# v1_E7.net
KiCad netlist of a schematic drawn in EAGLE
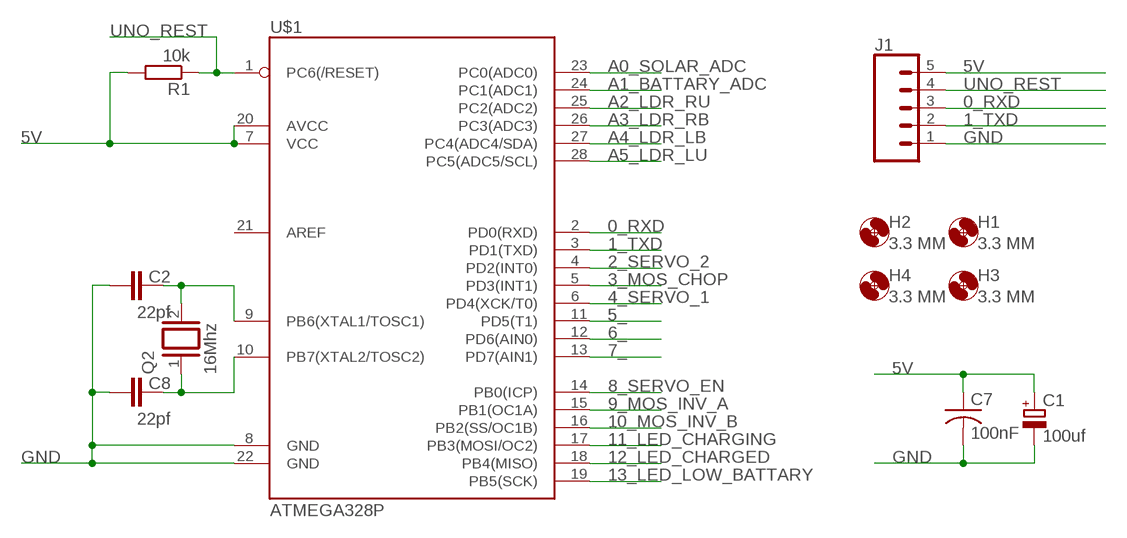
[diagram p0: schematic, sheet 1]
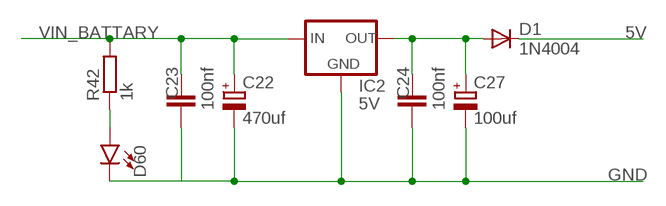
[diagram p1: schematic, sheet 2]
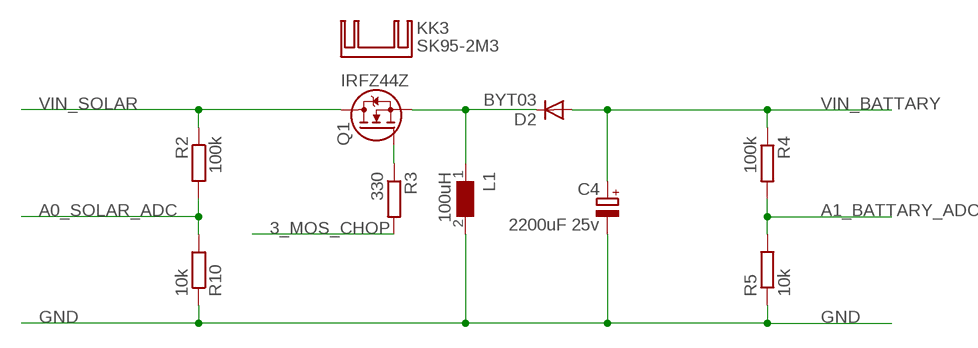
[diagram p2: schematic, sheet 3]
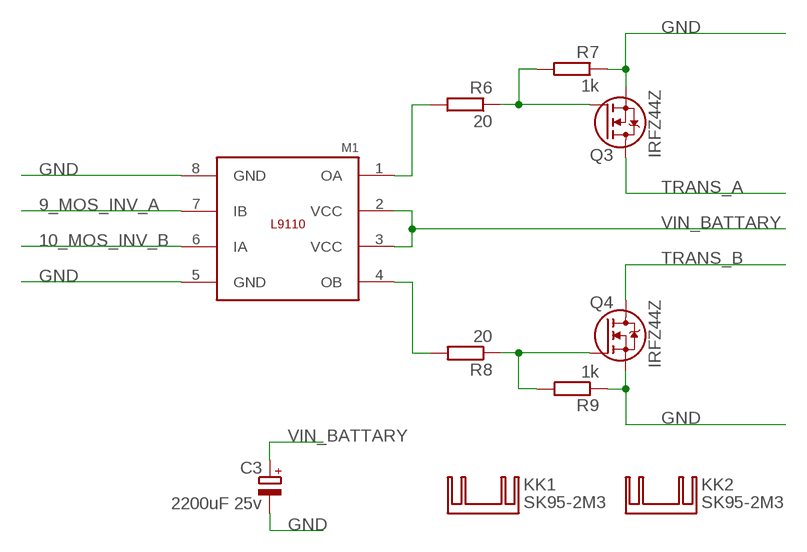
[diagram p3: schematic, sheet 4]
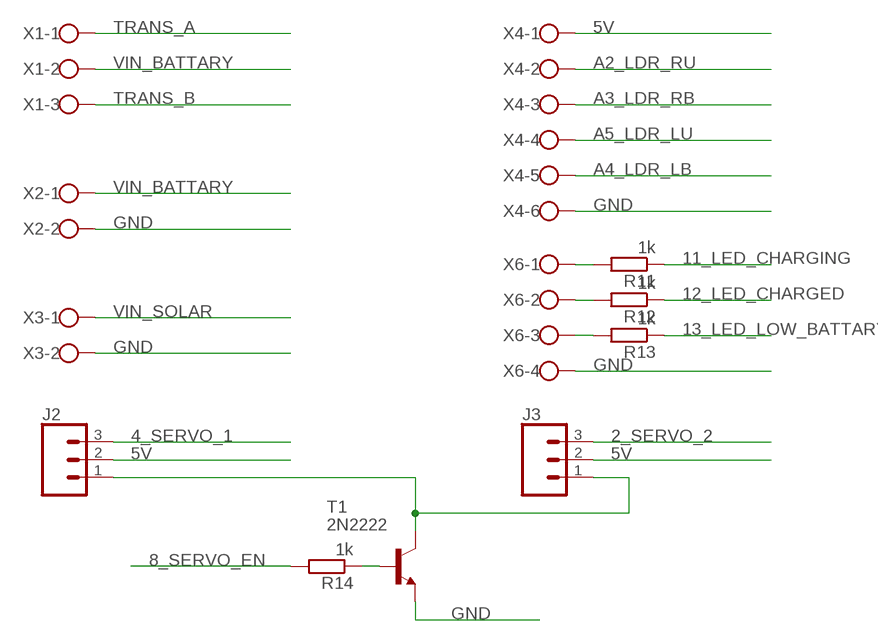
[diagram p4: schematic, sheet 5]

(export (version "E")
  (design (tool "Eeschema 10.0.6"))
  (components
    (comp (ref "C4")
      (value "2200uF 25v")
      (footprint "eagle-import:E5-13")
      (libsource (lib "eagle-import") (part "rcl@1_CPOL-EUE5-13"))
    )
    (comp (ref "D2")
      (value "BYT03")
      (footprint "eagle-import:DO27-15")
      (libsource (lib "eagle-import") (part "BYT03"))
    )
    (comp (ref "KK3")
      (value "SK95-2M3")
      (footprint "eagle-import:SK95-2M3")
      (libsource (lib "eagle-import") (part "SK95-2M3"))
    )
    (comp (ref "L1")
      (value "100uH")
      (footprint "eagle-import:WE-ZB")
      (libsource (lib "eagle-import") (part "WE-ZB"))
    )
    (comp (ref "Q1")
      (value "IRFZ44Z")
      (footprint "eagle-import:TO220V")
      (libsource (lib "eagle-import") (part "IRFZ44Z"))
    )
    (comp (ref "R2")
      (value "100k")
      (footprint "eagle-import:0207_10")
      (libsource (lib "eagle-import") (part "R-EU_0207/10"))
    )
    (comp (ref "R3")
      (value "330")
      (footprint "eagle-import:0207_10")
      (libsource (lib "eagle-import") (part "R-EU_0207/10"))
    )
    (comp (ref "R4")
      (value "100k")
      (footprint "eagle-import:0207_10")
      (libsource (lib "eagle-import") (part "R-EU_0207/10"))
    )
    (comp (ref "R5")
      (value "10k")
      (footprint "eagle-import:0207_10")
      (libsource (lib "eagle-import") (part "R-EU_0207/10"))
    )
    (comp (ref "R10")
      (value "10k")
      (footprint "eagle-import:0207_10")
      (libsource (lib "eagle-import") (part "R-EU_0207/10"))
    )
    (comp (ref "C1")
      (value "100uf")
      (footprint "eagle-import:E3,5-8")
      (libsource (lib "eagle-import") (part "CPOL-EUE3.5-8"))
    )
    (comp (ref "C2")
      (value "22pf")
      (footprint "eagle-import:C050-030X075")
      (libsource (lib "eagle-import") (part "C-EU050-030X075"))
    )
    (comp (ref "C7")
      (value "100nF")
      (footprint "eagle-import:C050-035X075")
      (libsource (lib "eagle-import") (part "C-US050-035X075"))
    )
    (comp (ref "C8")
      (value "22pf")
      (footprint "eagle-import:C050-030X075")
      (libsource (lib "eagle-import") (part "C-EU050-030X075"))
    )
    (comp (ref "H1")
      (value "3.3 MM")
      (footprint "eagle-import:3,3")
      (libsource (lib "eagle-import") (part "MOUNT-HOLE3.3"))
    )
    (comp (ref "H2")
      (value "3.3 MM")
      (footprint "eagle-import:3,3")
      (libsource (lib "eagle-import") (part "MOUNT-HOLE3.3"))
    )
    (comp (ref "H3")
      (value "3.3 MM")
      (footprint "eagle-import:3,3")
      (libsource (lib "eagle-import") (part "MOUNT-HOLE3.3"))
    )
    (comp (ref "H4")
      (value "3.3 MM")
      (footprint "eagle-import:3,3")
      (libsource (lib "eagle-import") (part "MOUNT-HOLE3.3"))
    )
    (comp (ref "J1")
      (value "CONN_05JST-VERT")
      (footprint "eagle-import:JST-5-PTH-VERT")
      (libsource (lib "eagle-import") (part "CONN_05JST-VERT"))
    )
    (comp (ref "Q2")
      (value "16Mhz")
      (footprint "eagle-import:QS")
      (libsource (lib "eagle-import") (part "XTAL/S"))
    )
    (comp (ref "R1")
      (value "10k")
      (footprint "eagle-import:0207_10")
      (libsource (lib "eagle-import") (part "R-EU_0207/10"))
    )
    (comp (ref "U$1")
      (value "ATMEGA328P")
      (footprint "eagle-import:DIL-28-3")
      (libsource (lib "eagle-import") (part "ATMEGA328P_PDIP"))
    )
    (comp (ref "C22")
      (value "470uf")
      (footprint "eagle-import:E3,5-8")
      (libsource (lib "eagle-import") (part "CPOL-EUE3.5-8"))
    )
    (comp (ref "C23")
      (value "100nf")
      (footprint "eagle-import:C050-030X075")
      (libsource (lib "eagle-import") (part "C-EU050-030X075"))
    )
    (comp (ref "C24")
      (value "100nf")
      (footprint "eagle-import:C050-030X075")
      (libsource (lib "eagle-import") (part "C-EU050-030X075"))
    )
    (comp (ref "C27")
      (value "100uf")
      (footprint "eagle-import:E3,5-8")
      (libsource (lib "eagle-import") (part "CPOL-EUE3.5-8"))
    )
    (comp (ref "D1")
      (value "1N4004")
      (footprint "eagle-import:DO41-10")
      (libsource (lib "eagle-import") (part "1N4004"))
    )
    (comp (ref "D60")
      (value "LED5MM")
      (footprint "eagle-import:LED_5MM")
      (libsource (lib "eagle-import") (part "LED5MM"))
    )
    (comp (ref "IC2")
      (value "5V")
      (footprint "eagle-import:78XXL")
      (libsource (lib "eagle-import") (part "V_REG_78XXSIDE"))
    )
    (comp (ref "R42")
      (value "1k")
      (footprint "eagle-import:0207_10")
      (libsource (lib "eagle-import") (part "R-EU_0207/10"))
    )
    (comp (ref "C3")
      (value "2200uF 25v")
      (footprint "eagle-import:E5-13")
      (libsource (lib "eagle-import") (part "rcl@1_CPOL-EUE5-13"))
    )
    (comp (ref "KK1")
      (value "SK95-2M3")
      (footprint "eagle-import:SK95-2M3")
      (libsource (lib "eagle-import") (part "SK95-2M3"))
    )
    (comp (ref "KK2")
      (value "SK95-2M3")
      (footprint "eagle-import:SK95-2M3")
      (libsource (lib "eagle-import") (part "SK95-2M3"))
    )
    (comp (ref "M1")
      (value "L9110")
      (footprint "eagle-import:SO8P")
      (libsource (lib "eagle-import") (part "L9110"))
    )
    (comp (ref "Q3")
      (value "IRFZ44Z")
      (footprint "eagle-import:TO220V")
      (libsource (lib "eagle-import") (part "IRFZ44Z"))
    )
    (comp (ref "Q4")
      (value "IRFZ44Z")
      (footprint "eagle-import:TO220V")
      (libsource (lib "eagle-import") (part "IRFZ44Z"))
    )
    (comp (ref "R6")
      (value "20")
      (footprint "eagle-import:0207_10")
      (libsource (lib "eagle-import") (part "R-EU_0207/10"))
    )
    (comp (ref "R7")
      (value "1k")
      (footprint "eagle-import:0207_10")
      (libsource (lib "eagle-import") (part "R-EU_0207/10"))
    )
    (comp (ref "R8")
      (value "20")
      (footprint "eagle-import:0207_10")
      (libsource (lib "eagle-import") (part "R-EU_0207/10"))
    )
    (comp (ref "R9")
      (value "1k")
      (footprint "eagle-import:0207_10")
      (libsource (lib "eagle-import") (part "R-EU_0207/10"))
    )
    (comp (ref "J2")
      (value "CONN_03JST-PTH-VERT")
      (footprint "eagle-import:JST-3-PTH-VERT")
      (libsource (lib "eagle-import") (part "CONN_03JST-PTH-VERT"))
    )
    (comp (ref "J3")
      (value "CONN_03JST-PTH-VERT")
      (footprint "eagle-import:JST-3-PTH-VERT")
      (libsource (lib "eagle-import") (part "CONN_03JST-PTH-VERT"))
    )
    (comp (ref "R11")
      (value "1k")
      (footprint "eagle-import:0207_10")
      (libsource (lib "eagle-import") (part "R-EU_0207/10"))
    )
    (comp (ref "R12")
      (value "1k")
      (footprint "eagle-import:0207_10")
      (libsource (lib "eagle-import") (part "R-EU_0207/10"))
    )
    (comp (ref "R13")
      (value "1k")
      (footprint "eagle-import:0207_10")
      (libsource (lib "eagle-import") (part "R-EU_0207/10"))
    )
    (comp (ref "R14")
      (value "1k")
      (footprint "eagle-import:0207_10")
      (libsource (lib "eagle-import") (part "R-EU_0207/10"))
    )
    (comp (ref "T1")
      (value "2N2222")
      (footprint "eagle-import:TO92-EBC-OVAL")
      (libsource (lib "eagle-import") (part "2N2222"))
    )
    (comp (ref "X1")
      (value "W237-103")
      (footprint "eagle-import:W237-103")
      (fields (field (name "MPN") "237-103"))
      (libsource (lib "eagle-import") (part "W237-103"))
    )
    (comp (ref "X2")
      (value "W237-102")
      (footprint "eagle-import:W237-102")
      (fields (field (name "MPN") "237-102"))
      (libsource (lib "eagle-import") (part "W237-102"))
    )
    (comp (ref "X3")
      (value "W237-102")
      (footprint "eagle-import:W237-102")
      (fields (field (name "MPN") "237-102"))
      (libsource (lib "eagle-import") (part "W237-102"))
    )
    (comp (ref "X4")
      (value "W237-6")
      (footprint "eagle-import:W237-6")
      (libsource (lib "eagle-import") (part "W237-6"))
    )
    (comp (ref "X6")
      (value "W237-4")
      (footprint "eagle-import:W237-4")
      (libsource (lib "eagle-import") (part "W237-4"))
    )
  )
  (nets
    (net (code "1") (name "0_RXD") (class "Default")
      (node (ref "J1") (pin "3") (pinfunction "3_3") (pintype "passive"))
      (node (ref "U$1") (pin "2") (pinfunction "PD0(RXD)_2") (pintype "bidirectional"))
    )
    (net (code "2") (name "1_TXD") (class "Default")
      (node (ref "J1") (pin "2") (pinfunction "2_2") (pintype "passive"))
      (node (ref "U$1") (pin "3") (pinfunction "PD1(TXD)_3") (pintype "bidirectional"))
    )
    (net (code "3") (name "2_SERVO_2") (class "Default")
      (node (ref "J3") (pin "3") (pinfunction "3_3") (pintype "passive"))
      (node (ref "U$1") (pin "4") (pinfunction "PD2(INT0)_4") (pintype "bidirectional"))
    )
    (net (code "4") (name "3_MOS_CHOP") (class "Default")
      (node (ref "R3") (pin "2") (pinfunction "2_2") (pintype "passive"))
      (node (ref "U$1") (pin "5") (pinfunction "PD3(INT1)_5") (pintype "bidirectional"))
    )
    (net (code "5") (name "4_SERVO_1") (class "Default")
      (node (ref "J2") (pin "3") (pinfunction "3_3") (pintype "passive"))
      (node (ref "U$1") (pin "6") (pinfunction "PD4(XCK/T0)_6") (pintype "bidirectional"))
    )
    (net (code "6") (name "5V") (class "Default")
      (node (ref "C1") (pin "+") (pinfunction "+_+") (pintype "passive"))
      (node (ref "C7") (pin "1") (pinfunction "1_1") (pintype "passive"))
      (node (ref "D1") (pin "C") (pinfunction "C_C") (pintype "passive"))
      (node (ref "J1") (pin "5") (pinfunction "5_5") (pintype "passive"))
      (node (ref "J2") (pin "2") (pinfunction "2_2") (pintype "passive"))
      (node (ref "J3") (pin "2") (pinfunction "2_2") (pintype "passive"))
      (node (ref "R1") (pin "2") (pinfunction "2_2") (pintype "passive"))
      (node (ref "U$1") (pin "20") (pinfunction "AVCC_20") (pintype "bidirectional"))
      (node (ref "U$1") (pin "7") (pinfunction "VCC_7") (pintype "bidirectional"))
      (node (ref "X4") (pin "1") (pinfunction "KL_1") (pintype "passive"))
    )
    (net (code "7") (name "5_") (class "Default")
      (node (ref "U$1") (pin "11") (pinfunction "PD5(T1)_11") (pintype "bidirectional"))
    )
    (net (code "8") (name "6_") (class "Default")
      (node (ref "U$1") (pin "12") (pinfunction "PD6(AIN0)_12") (pintype "bidirectional"))
    )
    (net (code "9") (name "7_") (class "Default")
      (node (ref "U$1") (pin "13") (pinfunction "PD7(AIN1)_13") (pintype "bidirectional"))
    )
    (net (code "10") (name "8_SERVO_EN") (class "Default")
      (node (ref "R14") (pin "2") (pinfunction "2_2") (pintype "passive"))
      (node (ref "U$1") (pin "14") (pinfunction "PB0(ICP)_14") (pintype "bidirectional"))
    )
    (net (code "11") (name "9_MOS_INV_A") (class "Default")
      (node (ref "M1") (pin "7") (pinfunction "IB_7") (pintype "bidirectional"))
      (node (ref "U$1") (pin "15") (pinfunction "PB1(OC1A)_15") (pintype "bidirectional"))
    )
    (net (code "12") (name "10_MOS_INV_B") (class "Default")
      (node (ref "M1") (pin "6") (pinfunction "IA_6") (pintype "bidirectional"))
      (node (ref "U$1") (pin "16") (pinfunction "PB2(SS/OC1B)_16") (pintype "bidirectional"))
    )
    (net (code "13") (name "11_LED_CHARGING") (class "Default")
      (node (ref "R11") (pin "1") (pinfunction "1_1") (pintype "passive"))
      (node (ref "U$1") (pin "17") (pinfunction "PB3(MOSI/OC2)_17") (pintype "bidirectional"))
    )
    (net (code "14") (name "12_LED_CHARGED") (class "Default")
      (node (ref "R12") (pin "1") (pinfunction "1_1") (pintype "passive"))
      (node (ref "U$1") (pin "18") (pinfunction "PB4(MISO)_18") (pintype "bidirectional"))
    )
    (net (code "15") (name "13_LED_LOW_BATTARY") (class "Default")
      (node (ref "R13") (pin "1") (pinfunction "1_1") (pintype "passive"))
      (node (ref "U$1") (pin "19") (pinfunction "PB5(SCK)_19") (pintype "bidirectional"))
    )
    (net (code "16") (name "A0_SOLAR_ADC") (class "Default")
      (node (ref "R10") (pin "2") (pinfunction "2_2") (pintype "passive"))
      (node (ref "R2") (pin "2") (pinfunction "2_2") (pintype "passive"))
      (node (ref "U$1") (pin "23") (pinfunction "PC0(ADC0)_23") (pintype "bidirectional"))
    )
    (net (code "17") (name "A1_BATTARY_ADC") (class "Default")
      (node (ref "R4") (pin "2") (pinfunction "2_2") (pintype "passive"))
      (node (ref "R5") (pin "2") (pinfunction "2_2") (pintype "passive"))
      (node (ref "U$1") (pin "24") (pinfunction "PC1(ADC1)_24") (pintype "bidirectional"))
    )
    (net (code "18") (name "A2_LDR_RU") (class "Default")
      (node (ref "U$1") (pin "25") (pinfunction "PC2(ADC2)_25") (pintype "bidirectional"))
      (node (ref "X4") (pin "2") (pinfunction "KL_2") (pintype "passive"))
    )
    (net (code "19") (name "A3_LDR_RB") (class "Default")
      (node (ref "U$1") (pin "26") (pinfunction "PC3(ADC3)_26") (pintype "bidirectional"))
      (node (ref "X4") (pin "3") (pinfunction "KL_3") (pintype "passive"))
    )
    (net (code "20") (name "A4_LDR_LB") (class "Default")
      (node (ref "U$1") (pin "27") (pinfunction "PC4(ADC4/SDA)_27") (pintype "bidirectional"))
      (node (ref "X4") (pin "5") (pinfunction "KL_5") (pintype "passive"))
    )
    (net (code "21") (name "A5_LDR_LU") (class "Default")
      (node (ref "U$1") (pin "28") (pinfunction "PC5(ADC5/SCL)_28") (pintype "bidirectional"))
      (node (ref "X4") (pin "4") (pinfunction "KL_4") (pintype "passive"))
    )
    (net (code "22") (name "GND") (class "Default")
      (node (ref "C1") (pin "-") (pinfunction "-_-") (pintype "passive"))
      (node (ref "C2") (pin "1") (pinfunction "1_1") (pintype "passive"))
      (node (ref "C22") (pin "-") (pinfunction "-_-") (pintype "passive"))
      (node (ref "C23") (pin "1") (pinfunction "1_1") (pintype "passive"))
      (node (ref "C24") (pin "1") (pinfunction "1_1") (pintype "passive"))
      (node (ref "C27") (pin "-") (pinfunction "-_-") (pintype "passive"))
      (node (ref "C3") (pin "-") (pinfunction "-_-") (pintype "passive"))
      (node (ref "C4") (pin "-") (pinfunction "-_-") (pintype "passive"))
      (node (ref "C7") (pin "2") (pinfunction "2_2") (pintype "passive"))
      (node (ref "C8") (pin "1") (pinfunction "1_1") (pintype "passive"))
      (node (ref "D60") (pin "K") (pinfunction "C_K") (pintype "passive"))
      (node (ref "IC2") (pin "GND") (pinfunction "GND_GND") (pintype "input"))
      (node (ref "J1") (pin "1") (pinfunction "1_1") (pintype "passive"))
      (node (ref "L1") (pin "2") (pinfunction "2_2") (pintype "passive"))
      (node (ref "M1") (pin "5") (pinfunction "GND_5") (pintype "bidirectional"))
      (node (ref "M1") (pin "8") (pinfunction "GND_8") (pintype "bidirectional"))
      (node (ref "Q3") (pin "3") (pinfunction "S_3") (pintype "passive"))
      (node (ref "Q4") (pin "3") (pinfunction "S_3") (pintype "passive"))
      (node (ref "R10") (pin "1") (pinfunction "1_1") (pintype "passive"))
      (node (ref "R5") (pin "1") (pinfunction "1_1") (pintype "passive"))
      (node (ref "R7") (pin "1") (pinfunction "1_1") (pintype "passive"))
      (node (ref "R9") (pin "1") (pinfunction "1_1") (pintype "passive"))
      (node (ref "T1") (pin "E") (pinfunction "E_E") (pintype "passive"))
      (node (ref "U$1") (pin "22") (pinfunction "GND_22") (pintype "bidirectional"))
      (node (ref "U$1") (pin "8") (pinfunction "GND_8") (pintype "bidirectional"))
      (node (ref "X2") (pin "2") (pinfunction "KL_2") (pintype "passive"))
      (node (ref "X3") (pin "2") (pinfunction "KL_2") (pintype "passive"))
      (node (ref "X4") (pin "6") (pinfunction "KL_6") (pintype "passive"))
      (node (ref "X6") (pin "4") (pinfunction "KL_4") (pintype "passive"))
    )
    (net (code "23") (name "Net-(C24-Pad2)") (class "Default")
      (node (ref "C24") (pin "2") (pinfunction "2_2") (pintype "passive"))
      (node (ref "C27") (pin "+") (pinfunction "+_+") (pintype "passive"))
      (node (ref "D1") (pin "A") (pinfunction "A_A") (pintype "passive"))
      (node (ref "IC2") (pin "OUT") (pinfunction "OUT_OUT") (pintype "output"))
    )
    (net (code "24") (name "Net-(D60-PadA)") (class "Default")
      (node (ref "D60") (pin "A") (pinfunction "A_A") (pintype "passive"))
      (node (ref "R42") (pin "1") (pinfunction "1_1") (pintype "passive"))
    )
    (net (code "25") (name "Net-(J2-Pad1)") (class "Default")
      (node (ref "J2") (pin "1") (pinfunction "1_1") (pintype "passive"))
      (node (ref "J3") (pin "1") (pinfunction "1_1") (pintype "passive"))
      (node (ref "T1") (pin "C") (pinfunction "C_C") (pintype "passive"))
    )
    (net (code "26") (name "Net-(M1-OA)") (class "Default")
      (node (ref "M1") (pin "1") (pinfunction "OA_1") (pintype "bidirectional"))
      (node (ref "R6") (pin "2") (pinfunction "2_2") (pintype "passive"))
    )
    (net (code "27") (name "Net-(M1-OB)") (class "Default")
      (node (ref "M1") (pin "4") (pinfunction "OB_4") (pintype "bidirectional"))
      (node (ref "R8") (pin "2") (pinfunction "2_2") (pintype "passive"))
    )
    (net (code "28") (name "Net-(Q1-G)") (class "Default")
      (node (ref "Q1") (pin "1") (pinfunction "G_1") (pintype "passive"))
      (node (ref "R3") (pin "1") (pinfunction "1_1") (pintype "passive"))
    )
    (net (code "29") (name "Net-(Q1-S)") (class "Default")
      (node (ref "D2") (pin "C") (pinfunction "C_C") (pintype "passive"))
      (node (ref "L1") (pin "1") (pinfunction "1_1") (pintype "passive"))
      (node (ref "Q1") (pin "3") (pinfunction "S_3") (pintype "passive"))
    )
    (net (code "30") (name "Net-(Q3-G)") (class "Default")
      (node (ref "Q3") (pin "1") (pinfunction "G_1") (pintype "passive"))
      (node (ref "R6") (pin "1") (pinfunction "1_1") (pintype "passive"))
      (node (ref "R7") (pin "2") (pinfunction "2_2") (pintype "passive"))
    )
    (net (code "31") (name "Net-(Q4-G)") (class "Default")
      (node (ref "Q4") (pin "1") (pinfunction "G_1") (pintype "passive"))
      (node (ref "R8") (pin "1") (pinfunction "1_1") (pintype "passive"))
      (node (ref "R9") (pin "2") (pinfunction "2_2") (pintype "passive"))
    )
    (net (code "32") (name "Net-(R14-Pad1)") (class "Default")
      (node (ref "R14") (pin "1") (pinfunction "1_1") (pintype "passive"))
      (node (ref "T1") (pin "B") (pinfunction "B_B") (pintype "passive"))
    )
    (net (code "33") (name "Net-(U$1-PB6(XTAL1{slash}TOSC1))") (class "Default")
      (node (ref "C2") (pin "2") (pinfunction "2_2") (pintype "passive"))
      (node (ref "Q2") (pin "2") (pinfunction "2_2") (pintype "passive"))
      (node (ref "U$1") (pin "9") (pinfunction "PB6(XTAL1/TOSC1)_9") (pintype "bidirectional"))
    )
    (net (code "34") (name "Net-(U$1-PB7(XTAL2{slash}TOSC2))") (class "Default")
      (node (ref "C8") (pin "2") (pinfunction "2_2") (pintype "passive"))
      (node (ref "Q2") (pin "1") (pinfunction "1_1") (pintype "passive"))
      (node (ref "U$1") (pin "10") (pinfunction "PB7(XTAL2/TOSC2)_10") (pintype "bidirectional"))
    )
    (net (code "35") (name "Net-(X6A-KL)") (class "Default")
      (node (ref "R11") (pin "2") (pinfunction "2_2") (pintype "passive"))
      (node (ref "X6") (pin "1") (pinfunction "KL_1") (pintype "passive"))
    )
    (net (code "36") (name "Net-(X6B-KL)") (class "Default")
      (node (ref "R12") (pin "2") (pinfunction "2_2") (pintype "passive"))
      (node (ref "X6") (pin "2") (pinfunction "KL_2") (pintype "passive"))
    )
    (net (code "37") (name "Net-(X6C-KL)") (class "Default")
      (node (ref "R13") (pin "2") (pinfunction "2_2") (pintype "passive"))
      (node (ref "X6") (pin "3") (pinfunction "KL_3") (pintype "passive"))
    )
    (net (code "38") (name "TRANS_A") (class "Default")
      (node (ref "Q3") (pin "2") (pinfunction "D_2") (pintype "passive"))
      (node (ref "X1") (pin "1") (pinfunction "KL_1") (pintype "passive"))
    )
    (net (code "39") (name "TRANS_B") (class "Default")
      (node (ref "Q4") (pin "2") (pinfunction "D_2") (pintype "passive"))
      (node (ref "X1") (pin "3") (pinfunction "KL_3") (pintype "passive"))
    )
    (net (code "40") (name "UNO_REST") (class "Default")
      (node (ref "J1") (pin "4") (pinfunction "4_4") (pintype "passive"))
      (node (ref "R1") (pin "1") (pinfunction "1_1") (pintype "passive"))
      (node (ref "U$1") (pin "1") (pinfunction "PC6(/RESET)_1") (pintype "bidirectional"))
    )
    (net (code "41") (name "VIN_BATTARY") (class "Default")
      (node (ref "C22") (pin "+") (pinfunction "+_+") (pintype "passive"))
      (node (ref "C23") (pin "2") (pinfunction "2_2") (pintype "passive"))
      (node (ref "C3") (pin "+") (pinfunction "+_+") (pintype "passive"))
      (node (ref "C4") (pin "+") (pinfunction "+_+") (pintype "passive"))
      (node (ref "D2") (pin "A") (pinfunction "A_A") (pintype "passive"))
      (node (ref "IC2") (pin "IN") (pinfunction "IN_IN") (pintype "input"))
      (node (ref "M1") (pin "2") (pinfunction "VCC_2") (pintype "bidirectional"))
      (node (ref "M1") (pin "3") (pinfunction "VCC_3") (pintype "bidirectional"))
      (node (ref "R4") (pin "1") (pinfunction "1_1") (pintype "passive"))
      (node (ref "R42") (pin "2") (pinfunction "2_2") (pintype "passive"))
      (node (ref "X1") (pin "2") (pinfunction "KL_2") (pintype "passive"))
      (node (ref "X2") (pin "1") (pinfunction "KL_1") (pintype "passive"))
    )
    (net (code "42") (name "VIN_SOLAR") (class "Default")
      (node (ref "Q1") (pin "2") (pinfunction "D_2") (pintype "passive"))
      (node (ref "R2") (pin "1") (pinfunction "1_1") (pintype "passive"))
      (node (ref "X3") (pin "1") (pinfunction "KL_1") (pintype "passive"))
    )
    (net (code "43") (name "unconnected-(U$1-AREF-Pad21)") (class "Default")
      (node (ref "U$1") (pin "21") (pinfunction "AREF_21") (pintype "bidirectional"))
    )
  )
)
